# so_do_nguyen_ly.net
KiCad netlist of a schematic drawn in Altium Designer
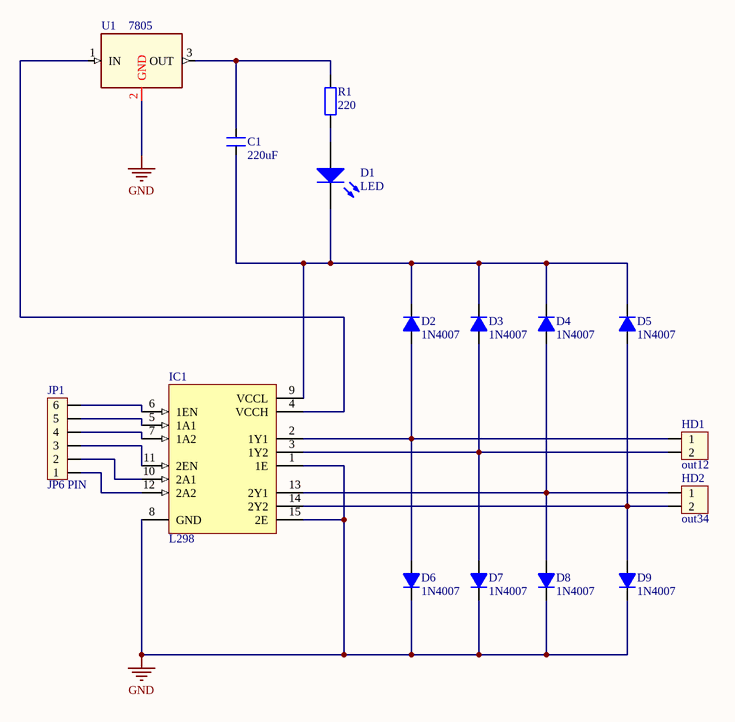
[diagram p0: so_do_nguyen_ly.SchDoc]

(export (version "E")
  (design (tool "Eeschema 10.0.6"))
  (components
    (comp (ref "C1")
      (value "220uF")
      (footprint "CN1.5")
      (description "Cap np 682pF => 104pF")
      (libsource (lib "hphonglib") (part "CN1.5"))
    )
    (comp (ref "D1")
      (value "LED")
      (footprint "LED-0 3mm RED")
      (description "Typical LED")
      (fields (field (name "PUBLISHER") "Altium Limited"))
      (libsource (lib "hphonglib") (part "LED"))
    )
    (comp (ref "D2")
      (value "1N4007")
      (footprint "D2A")
      (description "Diode 1A")
      (libsource (lib "hphonglib") (part "D1A"))
    )
    (comp (ref "D3")
      (value "1N4007")
      (footprint "D2A")
      (description "Diode 1A")
      (libsource (lib "hphonglib") (part "D1A"))
    )
    (comp (ref "D4")
      (value "1N4007")
      (footprint "D2A")
      (description "Diode 1A")
      (libsource (lib "hphonglib") (part "D1A"))
    )
    (comp (ref "D5")
      (value "1N4007")
      (footprint "D2A")
      (description "Diode 1A")
      (libsource (lib "hphonglib") (part "D1A"))
    )
    (comp (ref "D6")
      (value "1N4007")
      (footprint "D2A")
      (description "Diode 1A")
      (libsource (lib "hphonglib") (part "D1A"))
    )
    (comp (ref "D7")
      (value "1N4007")
      (footprint "D2A")
      (description "Diode 1A")
      (libsource (lib "hphonglib") (part "D1A"))
    )
    (comp (ref "D8")
      (value "1N4007")
      (footprint "D2A")
      (description "Diode 1A")
      (libsource (lib "hphonglib") (part "D1A"))
    )
    (comp (ref "D9")
      (value "1N4007")
      (footprint "D2A")
      (description "Diode 1A")
      (libsource (lib "hphonglib") (part "D1A"))
    )
    (comp (ref "HD1")
      (value "out12")
      (footprint "HED2")
      (description "Header 2 (Green)")
      (libsource (lib "hphonglib") (part "Hed2"))
    )
    (comp (ref "HD2")
      (value "out34")
      (footprint "HED2")
      (description "Header 2 (Green)")
      (libsource (lib "hphonglib") (part "Hed2"))
    )
    (comp (ref "IC1")
      (value "L298")
      (footprint "DIP15SL2")
      (description "Dual Full-H Driver")
      (fields (field (name "PUBLISHER") "Altium Limited"))
      (libsource (lib "hphonglib") (part "L298"))
    )
    (comp (ref "JP1") (value "JP6 PIN") (footprint "JP6") (libsource (lib "hphonglib") (part "JP6")))
    (comp (ref "R1")
      (value "220")
      (footprint "R1/4W")
      (description "Resistor 1/4W")
      (libsource (lib "hphonglib") (part "R1/4W"))
    )
    (comp (ref "U1")
      (value "LM78xx")
      (footprint "TO-220")
      (description "Regulator")
      (fields
        (field (name "MANUFACTURER") "Fairchild Semiconductor Corporation")
        (field (name "TOLERANCE") "4 %")
        (field (name "PUBLISHER") "Hoang Nguyen")
      )
      (libsource (lib "hphonglib") (part "LM78xx"))
    )
  )
  (nets
    (net (code "1") (name "GND") (class "Default")
      (node (ref "D6") (pin "2") (pinfunction "K_2") (pintype "passive"))
      (node (ref "D7") (pin "2") (pinfunction "K_2") (pintype "passive"))
      (node (ref "D8") (pin "2") (pinfunction "K_2") (pintype "passive"))
      (node (ref "D9") (pin "2") (pinfunction "K_2") (pintype "passive"))
      (node (ref "IC1") (pin "1") (pinfunction "1E_1") (pintype "passive"))
      (node (ref "IC1") (pin "15") (pinfunction "2E_15") (pintype "passive"))
      (node (ref "IC1") (pin "8") (pinfunction "GND_8") (pintype "power_in"))
      (node (ref "U1") (pin "2") (pinfunction "GND_2") (pintype "power_in"))
    )
    (net (code "2") (name "Net-(D1-A)") (class "Default")
      (node (ref "D1") (pin "1") (pinfunction "A_1") (pintype "passive"))
      (node (ref "R1") (pin "1") (pinfunction "1_1") (pintype "passive"))
    )
    (net (code "3") (name "Net-(D1-K)") (class "Default")
      (node (ref "C1") (pin "1") (pinfunction "1_1") (pintype "passive"))
      (node (ref "D1") (pin "2") (pinfunction "K_2") (pintype "passive"))
      (node (ref "D2") (pin "2") (pinfunction "K_2") (pintype "passive"))
      (node (ref "D3") (pin "2") (pinfunction "K_2") (pintype "passive"))
      (node (ref "D4") (pin "2") (pinfunction "K_2") (pintype "passive"))
      (node (ref "D5") (pin "2") (pinfunction "K_2") (pintype "passive"))
      (node (ref "IC1") (pin "9") (pinfunction "VCCL_9") (pintype "power_in"))
    )
    (net (code "4") (name "Net-(D2-A)") (class "Default")
      (node (ref "D2") (pin "1") (pinfunction "A_1") (pintype "passive"))
      (node (ref "D6") (pin "1") (pinfunction "A_1") (pintype "passive"))
      (node (ref "HD1") (pin "1") (pinfunction "1_1") (pintype "passive"))
      (node (ref "IC1") (pin "2") (pinfunction "1Y1_2") (pintype "tri_state"))
    )
    (net (code "5") (name "Net-(D3-A)") (class "Default")
      (node (ref "D3") (pin "1") (pinfunction "A_1") (pintype "passive"))
      (node (ref "D7") (pin "1") (pinfunction "A_1") (pintype "passive"))
      (node (ref "HD1") (pin "2") (pinfunction "2_2") (pintype "passive"))
      (node (ref "IC1") (pin "3") (pinfunction "1Y2_3") (pintype "tri_state"))
    )
    (net (code "6") (name "Net-(D4-A)") (class "Default")
      (node (ref "D4") (pin "1") (pinfunction "A_1") (pintype "passive"))
      (node (ref "D8") (pin "1") (pinfunction "A_1") (pintype "passive"))
      (node (ref "HD2") (pin "1") (pinfunction "1_1") (pintype "passive"))
      (node (ref "IC1") (pin "13") (pinfunction "2Y1_13") (pintype "tri_state"))
    )
    (net (code "7") (name "Net-(D5-A)") (class "Default")
      (node (ref "D5") (pin "1") (pinfunction "A_1") (pintype "passive"))
      (node (ref "D9") (pin "1") (pinfunction "A_1") (pintype "passive"))
      (node (ref "HD2") (pin "2") (pinfunction "2_2") (pintype "passive"))
      (node (ref "IC1") (pin "14") (pinfunction "2Y2_14") (pintype "tri_state"))
    )
    (net (code "8") (name "Net-(IC1-1A1)") (class "Default")
      (node (ref "IC1") (pin "5") (pinfunction "1A1_5") (pintype "input"))
      (node (ref "JP1") (pin "5") (pinfunction "5_5") (pintype "passive"))
    )
    (net (code "9") (name "Net-(IC1-1A2)") (class "Default")
      (node (ref "IC1") (pin "7") (pinfunction "1A2_7") (pintype "input"))
      (node (ref "JP1") (pin "4") (pinfunction "4_4") (pintype "passive"))
    )
    (net (code "10") (name "Net-(IC1-1EN)") (class "Default")
      (node (ref "IC1") (pin "6") (pinfunction "1EN_6") (pintype "input"))
      (node (ref "JP1") (pin "6") (pinfunction "6_6") (pintype "passive"))
    )
    (net (code "11") (name "Net-(IC1-2A1)") (class "Default")
      (node (ref "IC1") (pin "10") (pinfunction "2A1_10") (pintype "input"))
      (node (ref "JP1") (pin "2") (pinfunction "2_2") (pintype "passive"))
    )
    (net (code "12") (name "Net-(IC1-2A2)") (class "Default")
      (node (ref "IC1") (pin "12") (pinfunction "2A2_12") (pintype "input"))
      (node (ref "JP1") (pin "1") (pinfunction "1_1") (pintype "passive"))
    )
    (net (code "13") (name "Net-(IC1-2EN)") (class "Default")
      (node (ref "IC1") (pin "11") (pinfunction "2EN_11") (pintype "input"))
      (node (ref "JP1") (pin "3") (pinfunction "3_3") (pintype "passive"))
    )
    (net (code "14") (name "Net-(IC1-VCCH)") (class "Default")
      (node (ref "IC1") (pin "4") (pinfunction "VCCH_4") (pintype "power_in"))
      (node (ref "U1") (pin "1") (pinfunction "IN_1") (pintype "input"))
    )
    (net (code "15") (name "Net-(U1-OUT)") (class "Default")
      (node (ref "C1") (pin "2") (pinfunction "2_2") (pintype "passive"))
      (node (ref "R1") (pin "2") (pinfunction "2_2") (pintype "passive"))
      (node (ref "U1") (pin "3") (pinfunction "OUT_3") (pintype "output"))
    )
  )
)
